# buffered_input_11-4-21-fix.net
KiCad netlist of a schematic drawn in EAGLE
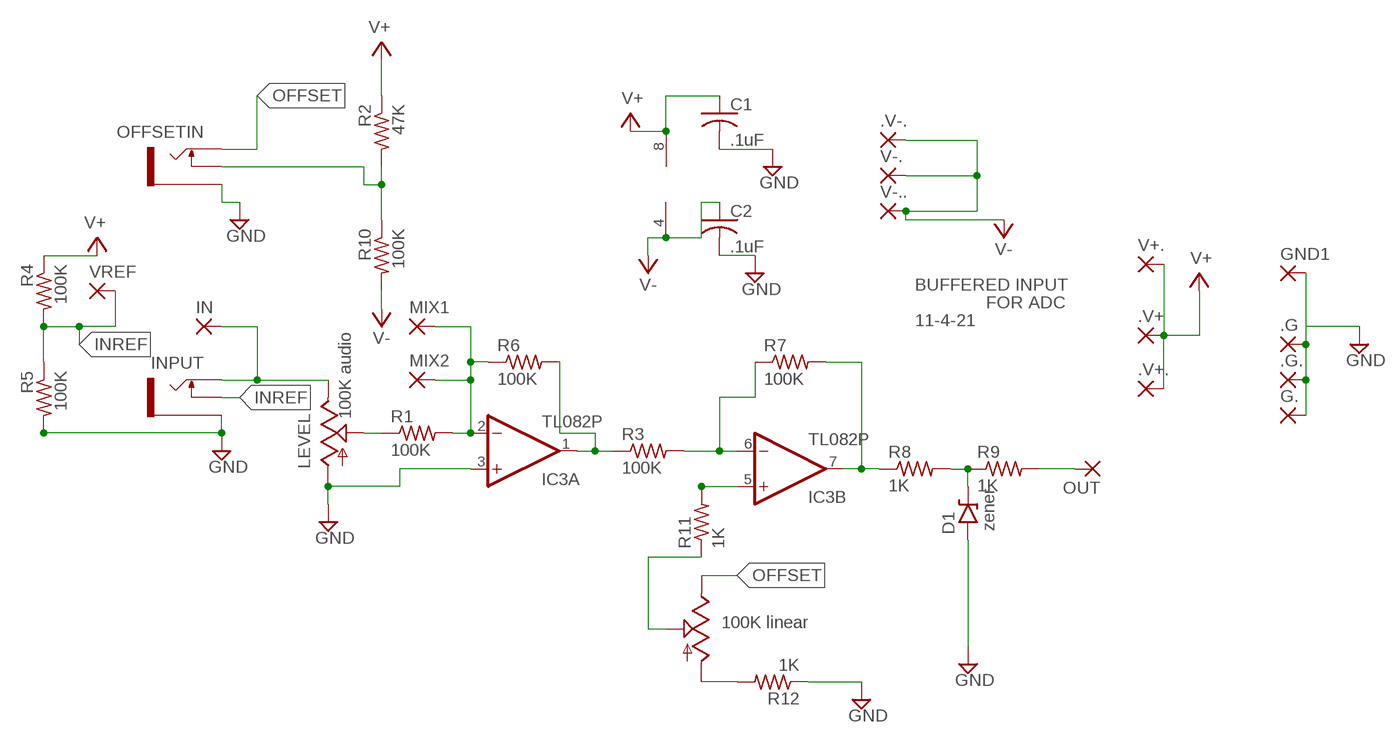
[diagram p0: schematic, sheet 1]

(export (version "E")
  (design (tool "Eeschema 10.0.6"))
  (components
    (comp (ref ".G")
      (value "3,17/1,3")
      (footprint "eagle-import:3,17_1,3")
      (libsource (lib "eagle-import") (part "wirepad_412_3,17/1,3"))
    )
    (comp (ref ".G.")
      (value "3,17/1,3")
      (footprint "eagle-import:3,17_1,3")
      (libsource (lib "eagle-import") (part "wirepad_412_3,17/1,3"))
    )
    (comp (ref ".V+")
      (value "2,54/1,0")
      (footprint "eagle-import:2,54_1,0")
      (libsource (lib "eagle-import") (part "2,54/1,0"))
    )
    (comp (ref ".V+.")
      (value "2,54/1,0")
      (footprint "eagle-import:2,54_1,0")
      (libsource (lib "eagle-import") (part "2,54/1,0"))
    )
    (comp (ref ".V-.")
      (value "3,17/1,3")
      (footprint "eagle-import:3,17_1,3")
      (libsource (lib "eagle-import") (part "3,17/1,3"))
    )
    (comp (ref "C1")
      (value ".1uF")
      (footprint "eagle-import:C025-025X050")
      (libsource (lib "eagle-import") (part "C-US025-025X050"))
    )
    (comp (ref "C2")
      (value ".1uF")
      (footprint "eagle-import:C025-025X050")
      (libsource (lib "eagle-import") (part "C-US025-025X050"))
    )
    (comp (ref "D1")
      (value "zener")
      (footprint "eagle-import:DO41-2")
      (libsource (lib "eagle-import") (part "ZENER.2"))
    )
    (comp (ref "G.")
      (value "3,17/1,3")
      (footprint "eagle-import:3,17_1,3")
      (libsource (lib "eagle-import") (part "wirepad_412_3,17/1,3"))
    )
    (comp (ref "GND1")
      (value "3,17/1,3")
      (footprint "eagle-import:3,17_1,3")
      (libsource (lib "eagle-import") (part "wirepad_412_3,17/1,3"))
    )
    (comp (ref "IC3")
      (value "TL082P")
      (footprint "eagle-import:DIL08")
      (libsource (lib "eagle-import") (part "TL082P"))
    )
    (comp (ref "IN")
      (value "3,17/1,3")
      (footprint "eagle-import:3,17_1,3")
      (libsource (lib "eagle-import") (part "wirepad_412_3,17/1,3"))
    )
    (comp (ref "INPUT")
      (value "THONKICONNNEW")
      (footprint "eagle-import:WQP-PJ301M-12_JACK")
      (libsource (lib "eagle-import") (part "THONKICONNNEW"))
    )
    (comp (ref "LEVEL")
      (value "100K audio")
      (footprint "eagle-import:9MM_SNAP-IN_POT")
      (libsource (lib "eagle-import") (part "9MM_SNAP-IN_POT_"))
    )
    (comp (ref "MIX1")
      (value "3,17/1,3")
      (footprint "eagle-import:3,17_1,3")
      (libsource (lib "eagle-import") (part "wirepad_412_3,17/1,3"))
    )
    (comp (ref "MIX2")
      (value "3,17/1,3")
      (footprint "eagle-import:3,17_1,3")
      (libsource (lib "eagle-import") (part "wirepad_412_3,17/1,3"))
    )
    (comp (ref "OFFSET")
      (value "100K linear")
      (footprint "eagle-import:9MM_SNAP-IN_POT")
      (libsource (lib "eagle-import") (part "9MM_SNAP-IN_POT_"))
    )
    (comp (ref "OFFSETIN")
      (value "THONKICONNNEW")
      (footprint "eagle-import:WQP-PJ301M-12_JACK")
      (libsource (lib "eagle-import") (part "THONKICONNNEW"))
    )
    (comp (ref "OUT")
      (value "3,17/1,3")
      (footprint "eagle-import:3,17_1,3")
      (libsource (lib "eagle-import") (part "wirepad_412_3,17/1,3"))
    )
    (comp (ref "R1")
      (value "100K")
      (footprint "eagle-import:0204_7")
      (libsource (lib "eagle-import") (part "R-US_0204/7"))
    )
    (comp (ref "R2")
      (value "47K")
      (footprint "eagle-import:0204_7")
      (libsource (lib "eagle-import") (part "R-US_0204/7"))
    )
    (comp (ref "R3")
      (value "100K")
      (footprint "eagle-import:0204_7")
      (libsource (lib "eagle-import") (part "R-US_0204/7"))
    )
    (comp (ref "R4")
      (value "100K")
      (footprint "eagle-import:0204_7")
      (libsource (lib "eagle-import") (part "R-US_0204/7"))
    )
    (comp (ref "R5")
      (value "100K")
      (footprint "eagle-import:0204_7")
      (libsource (lib "eagle-import") (part "R-US_0204/7"))
    )
    (comp (ref "R6")
      (value "100K")
      (footprint "eagle-import:0204_7")
      (libsource (lib "eagle-import") (part "R-US_0204/7"))
    )
    (comp (ref "R7")
      (value "100K")
      (footprint "eagle-import:0204_7")
      (libsource (lib "eagle-import") (part "R-US_0204/7"))
    )
    (comp (ref "R8")
      (value "1K")
      (footprint "eagle-import:0204_7")
      (libsource (lib "eagle-import") (part "R-US_0204/7"))
    )
    (comp (ref "R9")
      (value "1K")
      (footprint "eagle-import:0204_7")
      (libsource (lib "eagle-import") (part "R-US_0204/7"))
    )
    (comp (ref "R10")
      (value "100K")
      (footprint "eagle-import:0204_7")
      (libsource (lib "eagle-import") (part "R-US_0204/7"))
    )
    (comp (ref "R11")
      (value "1K")
      (footprint "eagle-import:0204_7")
      (libsource (lib "eagle-import") (part "R-US_0204/7"))
    )
    (comp (ref "R12")
      (value "1K")
      (footprint "eagle-import:0204_7")
      (libsource (lib "eagle-import") (part "R-US_0204/7"))
    )
    (comp (ref "V+.")
      (value "2,54/1,0")
      (footprint "eagle-import:2,54_1,0")
      (libsource (lib "eagle-import") (part "2,54/1,0"))
    )
    (comp (ref "V-.")
      (value "3,17/1,3")
      (footprint "eagle-import:3,17_1,3")
      (libsource (lib "eagle-import") (part "3,17/1,3"))
    )
    (comp (ref "V-..")
      (value "3,17/1,3")
      (footprint "eagle-import:3,17_1,3")
      (libsource (lib "eagle-import") (part "3,17/1,3"))
    )
    (comp (ref "VREF")
      (value "3,17/1,3")
      (footprint "eagle-import:3,17_1,3")
      (libsource (lib "eagle-import") (part "wirepad_412_3,17/1,3"))
    )
  )
  (nets
    (net (code "1") (name "GND") (class "Default")
      (node (ref ".G") (pin "1") (pinfunction "P_1") (pintype "passive"))
      (node (ref ".G.") (pin "1") (pinfunction "P_1") (pintype "passive"))
      (node (ref "C1") (pin "2") (pinfunction "2_2") (pintype "passive"))
      (node (ref "C2") (pin "2") (pinfunction "2_2") (pintype "passive"))
      (node (ref "D1") (pin "A") (pinfunction "A_A") (pintype "passive"))
      (node (ref "G.") (pin "1") (pinfunction "P_1") (pintype "passive"))
      (node (ref "GND1") (pin "1") (pinfunction "P_1") (pintype "passive"))
      (node (ref "IC3") (pin "3") (pinfunction "+IN_3") (pintype "input"))
      (node (ref "INPUT") (pin "P$3_SLEEVE") (pinfunction "SLEEVE_P$3_SLEEVE") (pintype "passive"))
      (node (ref "LEVEL") (pin "1") (pinfunction "A_1") (pintype "passive"))
      (node (ref "OFFSETIN") (pin "P$3_SLEEVE") (pinfunction "SLEEVE_P$3_SLEEVE") (pintype "passive"))
      (node (ref "R12") (pin "1") (pinfunction "1_1") (pintype "passive"))
      (node (ref "R5") (pin "2") (pinfunction "2_2") (pintype "passive"))
    )
    (net (code "2") (name "INREF") (class "Default")
      (node (ref "INPUT") (pin "P$2_SWITCH") (pinfunction "SWITCH_P$2_SWITCH") (pintype "passive"))
      (node (ref "R4") (pin "2") (pinfunction "2_2") (pintype "passive"))
      (node (ref "R5") (pin "1") (pinfunction "1_1") (pintype "passive"))
      (node (ref "VREF") (pin "1") (pinfunction "P_1") (pintype "passive"))
    )
    (net (code "3") (name "Net-(D1-PadC)") (class "Default")
      (node (ref "D1") (pin "C") (pinfunction "C_C") (pintype "passive"))
      (node (ref "R8") (pin "2") (pinfunction "2_2") (pintype "passive"))
      (node (ref "R9") (pin "1") (pinfunction "1_1") (pintype "passive"))
    )
    (net (code "4") (name "Net-(IC3A--IN)") (class "Default")
      (node (ref "IC3") (pin "2") (pinfunction "-IN_2") (pintype "input"))
      (node (ref "MIX1") (pin "1") (pinfunction "P_1") (pintype "passive"))
      (node (ref "MIX2") (pin "1") (pinfunction "P_1") (pintype "passive"))
      (node (ref "R1") (pin "2") (pinfunction "2_2") (pintype "passive"))
      (node (ref "R6") (pin "1") (pinfunction "1_1") (pintype "passive"))
    )
    (net (code "5") (name "Net-(IC3A-OUT)") (class "Default")
      (node (ref "IC3") (pin "1") (pinfunction "OUT_1") (pintype "output"))
      (node (ref "R3") (pin "1") (pinfunction "1_1") (pintype "passive"))
      (node (ref "R6") (pin "2") (pinfunction "2_2") (pintype "passive"))
    )
    (net (code "6") (name "Net-(IC3B-+IN)") (class "Default")
      (node (ref "IC3") (pin "5") (pinfunction "+IN_5") (pintype "input"))
      (node (ref "R11") (pin "2") (pinfunction "2_2") (pintype "passive"))
    )
    (net (code "7") (name "Net-(IC3B--IN)") (class "Default")
      (node (ref "IC3") (pin "6") (pinfunction "-IN_6") (pintype "input"))
      (node (ref "R3") (pin "2") (pinfunction "2_2") (pintype "passive"))
      (node (ref "R7") (pin "1") (pinfunction "1_1") (pintype "passive"))
    )
    (net (code "8") (name "Net-(IC3B-OUT)") (class "Default")
      (node (ref "IC3") (pin "7") (pinfunction "OUT_7") (pintype "output"))
      (node (ref "R7") (pin "2") (pinfunction "2_2") (pintype "passive"))
      (node (ref "R8") (pin "1") (pinfunction "1_1") (pintype "passive"))
    )
    (net (code "9") (name "Net-(IN-P)") (class "Default")
      (node (ref "IN") (pin "1") (pinfunction "P_1") (pintype "passive"))
      (node (ref "INPUT") (pin "P$1_TIP") (pinfunction "TIP_P$1_TIP") (pintype "passive"))
      (node (ref "LEVEL") (pin "3") (pinfunction "E_3") (pintype "passive"))
    )
    (net (code "10") (name "Net-(LEVEL-S)") (class "Default")
      (node (ref "LEVEL") (pin "2") (pinfunction "S_2") (pintype "passive"))
      (node (ref "R1") (pin "1") (pinfunction "1_1") (pintype "passive"))
    )
    (net (code "11") (name "Net-(OFFSET-A)") (class "Default")
      (node (ref "OFFSET") (pin "1") (pinfunction "A_1") (pintype "passive"))
      (node (ref "R12") (pin "2") (pinfunction "2_2") (pintype "passive"))
    )
    (net (code "12") (name "Net-(OFFSET-S)") (class "Default")
      (node (ref "OFFSET") (pin "2") (pinfunction "S_2") (pintype "passive"))
      (node (ref "R11") (pin "1") (pinfunction "1_1") (pintype "passive"))
    )
    (net (code "13") (name "Net-(OFFSETIN-SWITCH)") (class "Default")
      (node (ref "OFFSETIN") (pin "P$2_SWITCH") (pinfunction "SWITCH_P$2_SWITCH") (pintype "passive"))
      (node (ref "R10") (pin "1") (pinfunction "1_1") (pintype "passive"))
      (node (ref "R2") (pin "2") (pinfunction "2_2") (pintype "passive"))
    )
    (net (code "14") (name "Net-(OUT-P)") (class "Default")
      (node (ref "OUT") (pin "1") (pinfunction "P_1") (pintype "passive"))
      (node (ref "R9") (pin "2") (pinfunction "2_2") (pintype "passive"))
    )
    (net (code "15") (name "OFFSET") (class "Default")
      (node (ref "OFFSET") (pin "3") (pinfunction "E_3") (pintype "passive"))
      (node (ref "OFFSETIN") (pin "P$1_TIP") (pinfunction "TIP_P$1_TIP") (pintype "passive"))
    )
    (net (code "16") (name "V+") (class "Default")
      (node (ref ".V+") (pin "1") (pinfunction "P_1") (pintype "passive"))
      (node (ref ".V+.") (pin "1") (pinfunction "P_1") (pintype "passive"))
      (node (ref "C1") (pin "1") (pinfunction "1_1") (pintype "passive"))
      (node (ref "IC3") (pin "8") (pinfunction "V+_8") (pintype "power_in"))
      (node (ref "R2") (pin "1") (pinfunction "1_1") (pintype "passive"))
      (node (ref "R4") (pin "1") (pinfunction "1_1") (pintype "passive"))
      (node (ref "V+.") (pin "1") (pinfunction "P_1") (pintype "passive"))
    )
    (net (code "17") (name "V-") (class "Default")
      (node (ref ".V-.") (pin "1") (pinfunction "P_1") (pintype "passive"))
      (node (ref "C2") (pin "1") (pinfunction "1_1") (pintype "passive"))
      (node (ref "IC3") (pin "4") (pinfunction "V-_4") (pintype "power_in"))
      (node (ref "R10") (pin "2") (pinfunction "2_2") (pintype "passive"))
      (node (ref "V-.") (pin "1") (pinfunction "P_1") (pintype "passive"))
      (node (ref "V-..") (pin "1") (pinfunction "P_1") (pintype "passive"))
    )
  )
)
